# Peggy_Receiver.net
KiCad netlist of a schematic drawn in Altium Designer
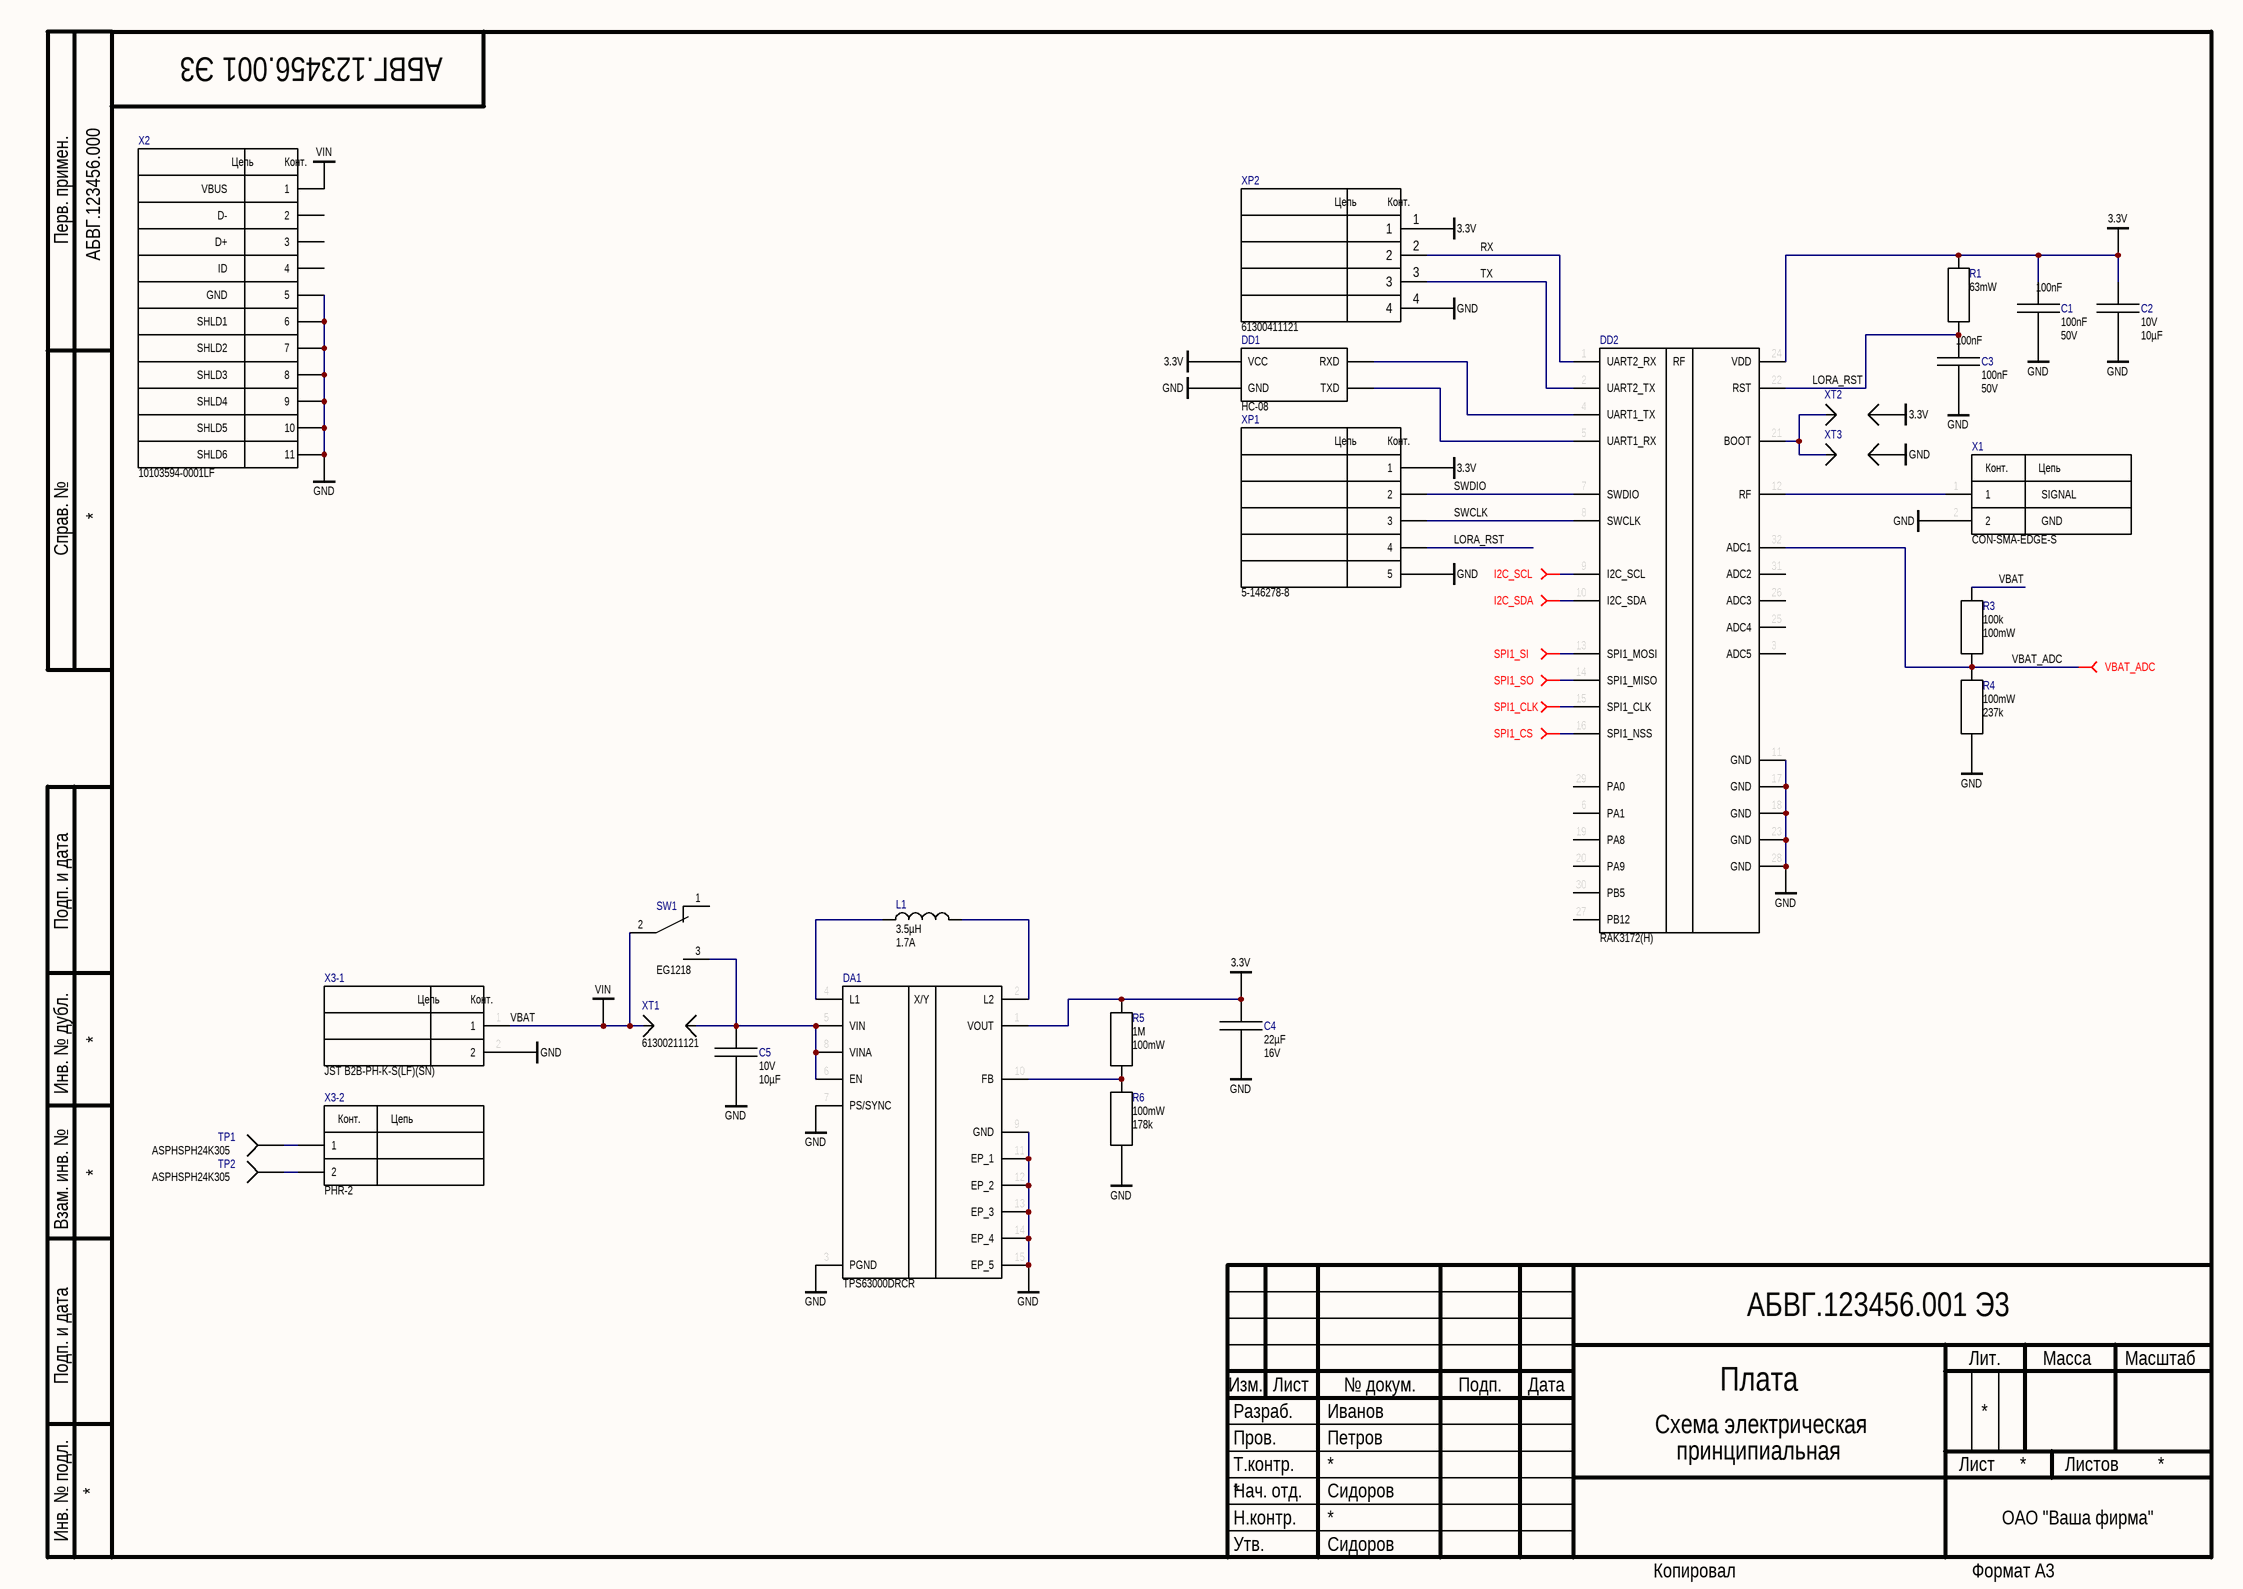
[diagram p0: Принципиальная схема Peggy Receiver.SchDoc]

(export (version "E")
  (design (tool "Eeschema 10.0.6"))
  (components
    (comp (ref "C1")
      (value "100nF")
      (footprint "CAPC1608X09M")
      (description "CAP CER 0.1UF 50V X7R 0603")
      (fields
        (field (name "VOLTAGE RATING") "50V")
        (field (name "TOLERANCE") "10%")
        (field (name "MANUFACTURER PART NUMBER") "GCM188R71H104KA57D")
        (field (name "CAPACITANCE") "100nF")
        (field (name "SOURCE") "Meteo_1.SCHLIB")
      )
      (libsource (lib "Sergek Concord Server") (part "CAP-NP-2"))
    )
    (comp (ref "C2")
      (value "10µF")
      (footprint "CAPC1608X87X35ML15T15")
      (description "Cap Ceramic 10uF 10V X5R 20% SMD 0603 85°C Paper T/R")
      (fields
        (field (name "VOLTAGE RATING") "10V")
        (field (name "TOLERANCE") "20%")
        (field (name "MANUFACTURER") "KEMET")
      )
      (libsource (lib "Sergek Concord Server") (part "CAP-NP-2"))
    )
    (comp (ref "C3")
      (value "100nF")
      (footprint "CAPC1608X09M")
      (description "CAP CER 0.1UF 50V X7R 0603")
      (fields
        (field (name "VOLTAGE RATING") "50V")
        (field (name "TOLERANCE") "10%")
        (field (name "MANUFACTURER PART NUMBER") "GCM188R71H104KA57D")
        (field (name "CAPACITANCE") "100nF")
        (field (name "SOURCE") "Meteo_1.SCHLIB")
      )
      (libsource (lib "Sergek Concord Server") (part "CAP-NP-2"))
    )
    (comp (ref "C4")
      (value "22µF")
      (footprint "CAPC2013X140X45ML15T25")
      (fields
        (field (name "VOLTAGE RATING") "16V")
        (field (name "TOLERANCE") "10%")
        (field (name "MANUFACTURER PART NUMBER") "C2012X5R1C226K125AC")
        (field (name "MANUFACTURER") "TDK")
      )
      (libsource (lib "Sergek Concord Server") (part "CAP-NP-2"))
    )
    (comp (ref "C5")
      (value "10µF")
      (footprint "CAPC1608X87X35ML15T15")
      (description "Cap Ceramic 10uF 10V X5R 20% SMD 0603 85°C Paper T/R")
      (fields
        (field (name "VOLTAGE RATING") "10V")
        (field (name "TOLERANCE") "20%")
        (field (name "MANUFACTURER") "KEMET")
      )
      (libsource (lib "Sergek Concord Server") (part "CAP-NP-2"))
    )
    (comp (ref "DA1")
      (value "TPS63000IDRCRQ1")
      (footprint "TPS63002DRCR")
      (description "IC REG BUCK BOOST ADJ 1.6A 10SON")
      (fields
        (field (name "MANUFACTURER PART NUMBER") "TPS63000DRCR")
        (field (name "MANUFACTURER") "Texas Instruments")
      )
      (libsource (lib "Sergek Concord Server") (part "TPS63000"))
    )
    (comp (ref "DD1")
      (value "HC-08")
      (footprint "HC-08")
      (description "Bluetooth 4.0 Module")
      (fields (field (name "MANUFACTURER PART NUMBER") "HC-08"))
      (libsource (lib "Sergek Concord Server") (part "HC-08"))
    )
    (comp (ref "DD2")
      (value "RAK3172(H)")
      (footprint "RAK3172(H)-Footprint-1")
      (description "RAK3172 WisDuo LPWAN Module")
      (fields
        (field (name "MANUFACTURER PART NUMBER") "RAK3172(H)")
        (field (name "MANUFACTURER") "RAK Wireless")
      )
      (libsource (lib "Sergek Concord Server") (part "RAK3172(H)"))
    )
    (comp (ref "I2C_SCL")
      (value "TP_1MM")
      (footprint "New footprint 1")
      (description "Test Point, 1mm diam")
      (fields (field (name "MANUFACTURER") "SRG_DEV"))
      (libsource (lib "Sergek Concord Server") (part "TP_1MM"))
    )
    (comp (ref "I2C_SDA")
      (value "TP_1MM")
      (footprint "New footprint 1")
      (description "Test Point, 1mm diam")
      (fields (field (name "MANUFACTURER") "SRG_DEV"))
      (libsource (lib "Sergek Concord Server") (part "TP_1MM"))
    )
    (comp (ref "L1")
      (value "3.5µH")
      (footprint "SRU5018680Y")
      (description "Ind Power Shielded Wirewound 3.5uH 30% 100KHz 9Q-Factor Ferrite 2.1A T/R")
      (fields
        (field (name "TOLERANCE") "30%")
        (field (name "SATURATION CURRENT") "1.7A")
        (field (name "MANUFACTURER") "Bourns")
      )
      (libsource (lib "Sergek Concord Server") (part "IND-2"))
    )
    (comp (ref "R1")
      (value "RNCF0603BTE10K0")
      (footprint "RESC1608X55X25ML10T15")
      (description "RES 10K OHM 0.1% 1/16W 0603")
      (fields (field (name "TOLERANCE") "0.1%") (field (name "POWER RATING") "63mW"))
      (libsource (lib "") (part "RES-2_1"))
    )
    (comp (ref "R3")
      (value "RMCF0603FT100K")
      (footprint "RESC1608X55X25ML10T15")
      (description "RES 100K OHM 1% 1/10W 0603")
      (fields
        (field (name "RESISTANCE") "100k")
        (field (name "MANUFACTURER") "Stackpole Electronics Inc")
        (field (name "TOLERANCE") "1%")
        (field (name "POWER RATING") "100mW")
      )
      (libsource (lib "Sergek Concord Server") (part "RES-2"))
    )
    (comp (ref "R4")
      (value "ERJ-3EKF2373V")
      (footprint "RESC1608X55X25ML10T15")
      (description "RES SMD 237K OHM 1% 1/10W 0603")
      (fields
        (field (name "POWER RATING") "100mW")
        (field (name "RESISTANCE") "237k")
        (field (name "TOLERANCE") "1%")
        (field (name "MANUFACTURER") "Panasonic")
      )
      (libsource (lib "Sergek Concord Server") (part "RES-2"))
    )
    (comp (ref "R5")
      (value "1M")
      (footprint "RESC1608X95X40ML15T20")
      (description "RES 1M OHM 5% 1/10W 0603")
      (fields
        (field (name "POWER RATING") "100mW")
        (field (name "TOLERANCE") "5%")
        (field (name "MANUFACTURER PART NUMBER") "RMCF0603JT1M00")
      )
      (libsource (lib "Sergek Concord Server") (part "RES-2"))
    )
    (comp (ref "R6")
      (value "178k")
      (footprint "RESC1608X95X40ML15T20")
      (fields
        (field (name "TOLERANCE") "1%")
        (field (name "POWER RATING") "100mW")
        (field (name "MANUFACTURER PART NUMBER") "ERJ-3EKF1783V")
        (field (name "MANUFACTURER") "Panasonic")
      )
      (libsource (lib "Sergek Concord Server") (part "RES-2"))
    )
    (comp (ref "SPI1_CLK")
      (value "TP_1MM")
      (footprint "New footprint 1")
      (description "Test Point, 1mm diam")
      (fields (field (name "MANUFACTURER") "SRG_DEV"))
      (libsource (lib "Sergek Concord Server") (part "TP_1MM"))
    )
    (comp (ref "SPI1_CS")
      (value "TP_1MM")
      (footprint "New footprint 1")
      (description "Test Point, 1mm diam")
      (fields (field (name "MANUFACTURER") "SRG_DEV"))
      (libsource (lib "Sergek Concord Server") (part "TP_1MM"))
    )
    (comp (ref "SPI1_SI")
      (value "TP_1MM")
      (footprint "New footprint 1")
      (description "Test Point, 1mm diam")
      (fields (field (name "MANUFACTURER") "SRG_DEV"))
      (libsource (lib "Sergek Concord Server") (part "TP_1MM"))
    )
    (comp (ref "SPI1_SO")
      (value "TP_1MM")
      (footprint "New footprint 1")
      (description "Test Point, 1mm diam")
      (fields (field (name "MANUFACTURER") "SRG_DEV"))
      (libsource (lib "Sergek Concord Server") (part "TP_1MM"))
    )
    (comp (ref "SW1")
      (value "EG1218")
      (footprint "ESWI-EG1218_V")
      (description "Slide Switch, SPDT, 500 V, -20 to 70 degC, 3-Pin THD, RoHS, Bulk")
      (fields (field (name "MANUFACTURER") "E-Switch") (field (name "MANUFACTURER PART NUMBER") "EG1218"))
      (libsource (lib "Sergek Concord Server") (part "SW-SPDT-3_B"))
    )
    (comp (ref "TP1")
      (value "ASPHSPH24K305")
      (description "Black 24 AWG Jumper Lead Socket to Socket Tin 12.0")
      (fields
        (field (name "MANUFACTURER") "JST Sales America Inc.")
        (field (name "MANUFACTURER PART NUMBER") "ASPHSPH24K305")
      )
      (libsource (lib "Sergek Concord Server") (part "JST_Metal_Contact"))
    )
    (comp (ref "TP2")
      (value "ASPHSPH24K305")
      (description "Black 24 AWG Jumper Lead Socket to Socket Tin 12.0")
      (fields
        (field (name "MANUFACTURER") "JST Sales America Inc.")
        (field (name "MANUFACTURER PART NUMBER") "ASPHSPH24K305")
      )
      (libsource (lib "Sergek Concord Server") (part "JST_Metal_Contact"))
    )
    (comp (ref "VBAT_ADC")
      (value "TP_1MM")
      (footprint "New footprint 1")
      (description "Test Point, 1mm diam")
      (fields (field (name "MANUFACTURER") "SRG_DEV"))
      (libsource (lib "Sergek Concord Server") (part "TP_1MM"))
    )
    (comp (ref "X1")
      (value "CON-SMA-EDGE-S")
      (footprint "RFSOLUTIONS_CON-SMA-EDGE-S")
      (description "CONN SMA JACK STR EDGE MNT")
      (fields
        (field (name "MANUFACTURER PART NUMBER") "CON-SMA-EDGE-S")
        (field (name "MANUFACTURER") "RF Solutions")
      )
      (libsource (lib "Sergek Concord Server") (part "CON-SMA-EDGE-S"))
    )
    (comp (ref "X2")
      (value "10103594-0001LF")
      (footprint "FCI-10103594-0001LF_V")
      (description "Micro USB 2.0 B Receptacle, 5 Position, Height 3.24 mm, -55 to 85 degC, RoHS, Tape and Reel")
      (fields
        (field (name "MANUFACTURER PART NUMBER") "10103594-0001LF")
        (field (name "MANUFACTURER") "Amphenol ICC (FCI)")
      )
      (libsource (lib "Sergek Concord Server") (part "USB-5-6SHLD"))
    )
    (comp (ref "X3-1")
      (value "B2B-PH-K-S")
      (footprint "JST-S2B-PH-K-S_V")
      (description "CONN HEADER VERT 2POS 2MM")
      (fields
        (field (name "MANUFACTURER PART NUMBER") "JST B2B-PH-K-S(LF)(SN)")
        (field (name "MANUFACTURER") "Japan Solderless Terminals")
      )
      (libsource (lib "Sergek Concord Server") (part "CN-1P-M-R2"))
    )
    (comp (ref "X3-2")
      (value "PHR-2")
      (description "CONN HOUSING PH 2POS 2MM WHITE")
      (fields (field (name "MANUFACTURER") "JST") (field (name "MANUFACTURER PART NUMBER") "PHR-2"))
      (libsource (lib "Sergek Concord Server") (part "X-2"))
    )
    (comp (ref "XP1")
      (value "5-146278-5")
      (footprint "5-146278-8-Footprint-1")
      (description "Conn Unshrouded Header HDR 5 POS 2.54mm Solder ST Thru-Hole Carton")
      (fields
        (field (name "MANUFACTURER PART NUMBER") "5-146278-8")
        (field (name "MANUFACTURER") "TE Connectivity")
      )
      (libsource (lib "Sergek Concord Server") (part "XP-5"))
    )
    (comp (ref "XP2")
      (value "61300411121")
      (footprint "20021311-00010T4LF-Footprint-1")
      (description "Conn Unshrouded Header HDR 4 POS 2.54mm Solder ST Thru-Hole Bag")
      (fields
        (field (name "MANUFACTURER") "Würth Elektronik")
        (field (name "MANUFACTURER PART NUMBER") "61300411121")
      )
      (libsource (lib "Sergek Concord Server") (part "XP-4"))
    )
    (comp (ref "XT1")
      (value "Jumper_1x2")
      (footprint "CON%3A PLS-2")
      (fields
        (field (name "MANUFACTURER") "Wurth Electronics")
        (field (name "MANUFACTURER PART NUMBER") "61300211121")
      )
      (libsource (lib "Sergek Concord Server") (part "Jumper 1x2"))
    )
    (comp (ref "XT2")
      (value "Jumper_solderable")
      (footprint "JUMPER-Footprint-2")
      (description "Solderable Jumper")
      (fields (field (name "MANUFACTURER PART NUMBER") "Home made"))
      (libsource (lib "Sergek Concord Server") (part "Jumper 1x2"))
    )
    (comp (ref "XT3")
      (value "Jumper_solderable")
      (footprint "JUMPER-Footprint-2")
      (description "Solderable Jumper")
      (fields (field (name "MANUFACTURER PART NUMBER") "Home made"))
      (libsource (lib "Sergek Concord Server") (part "Jumper 1x2"))
    )
  )
  (nets
    (net (code "1") (name "/LORA_RST") (class "Default")
      (node (ref "C3") (pin "2") (pinfunction "2_2") (pintype "passive"))
      (node (ref "DD2") (pin "22") (pinfunction "RST_22") (pintype "passive"))
      (node (ref "R1") (pin "2") (pinfunction "2_2") (pintype "passive"))
      (node (ref "XP1") (pin "4") (pinfunction "4_4") (pintype "passive"))
    )
    (net (code "2") (name "/RX") (class "Default")
      (node (ref "DD2") (pin "1") (pinfunction "UART2_RX_1") (pintype "passive"))
      (node (ref "XP2") (pin "2") (pinfunction "2_2") (pintype "passive"))
    )
    (net (code "3") (name "/SWCLK") (class "Default")
      (node (ref "DD2") (pin "8") (pinfunction "SWCLK_8") (pintype "passive"))
      (node (ref "XP1") (pin "3") (pinfunction "3_3") (pintype "passive"))
    )
    (net (code "4") (name "/SWDIO") (class "Default")
      (node (ref "DD2") (pin "7") (pinfunction "SWDIO_7") (pintype "passive"))
      (node (ref "XP1") (pin "2") (pinfunction "2_2") (pintype "passive"))
    )
    (net (code "5") (name "/TX") (class "Default")
      (node (ref "DD2") (pin "2") (pinfunction "UART2_TX_2") (pintype "passive"))
      (node (ref "XP2") (pin "3") (pinfunction "3_3") (pintype "passive"))
    )
    (net (code "6") (name "/VBAT_ADC") (class "Default")
      (node (ref "DD2") (pin "32") (pinfunction "ADC1_32") (pintype "passive"))
      (node (ref "R3") (pin "1") (pinfunction "1_1") (pintype "passive"))
      (node (ref "R4") (pin "2") (pinfunction "2_2") (pintype "passive"))
      (node (ref "VBAT_ADC") (pin "1") (pinfunction "1_1") (pintype "passive"))
    )
    (net (code "7") (name "3.3V") (class "Default")
      (node (ref "C1") (pin "2") (pinfunction "2_2") (pintype "passive"))
      (node (ref "C2") (pin "2") (pinfunction "2_2") (pintype "passive"))
      (node (ref "C4") (pin "2") (pinfunction "2_2") (pintype "passive"))
      (node (ref "DA1") (pin "1") (pinfunction "VOUT_1") (pintype "passive"))
      (node (ref "DD1") (pin "1") (pinfunction "VCC_1") (pintype "passive"))
      (node (ref "DD2") (pin "24") (pinfunction "VDD_24") (pintype "passive"))
      (node (ref "R1") (pin "1") (pinfunction "1_1") (pintype "passive"))
      (node (ref "R5") (pin "2") (pinfunction "2_2") (pintype "passive"))
      (node (ref "XP1") (pin "1") (pinfunction "1_1") (pintype "passive"))
      (node (ref "XP2") (pin "1") (pinfunction "1_1") (pintype "passive"))
      (node (ref "XT2") (pin "2") (pinfunction "2_2") (pintype "passive"))
    )
    (net (code "8") (name "GND") (class "Default")
      (node (ref "C1") (pin "1") (pinfunction "1_1") (pintype "passive"))
      (node (ref "C2") (pin "1") (pinfunction "1_1") (pintype "passive"))
      (node (ref "C3") (pin "1") (pinfunction "1_1") (pintype "passive"))
      (node (ref "C4") (pin "1") (pinfunction "1_1") (pintype "passive"))
      (node (ref "C5") (pin "1") (pinfunction "1_1") (pintype "passive"))
      (node (ref "DA1") (pin "11") (pinfunction "EP_1_11") (pintype "passive"))
      (node (ref "DA1") (pin "12") (pinfunction "EP_2_12") (pintype "passive"))
      (node (ref "DA1") (pin "13") (pinfunction "EP_3_13") (pintype "passive"))
      (node (ref "DA1") (pin "14") (pinfunction "EP_4_14") (pintype "passive"))
      (node (ref "DA1") (pin "15") (pinfunction "EP_5_15") (pintype "passive"))
      (node (ref "DA1") (pin "3") (pinfunction "PGND_3") (pintype "passive"))
      (node (ref "DA1") (pin "7") (pinfunction "PS/SYNC_7") (pintype "passive"))
      (node (ref "DA1") (pin "9") (pinfunction "GND_9") (pintype "passive"))
      (node (ref "DD1") (pin "2") (pinfunction "GND_2") (pintype "passive"))
      (node (ref "DD2") (pin "11") (pinfunction "GND_11") (pintype "passive"))
      (node (ref "DD2") (pin "17") (pinfunction "GND_17") (pintype "passive"))
      (node (ref "DD2") (pin "18") (pinfunction "GND_18") (pintype "passive"))
      (node (ref "DD2") (pin "23") (pinfunction "GND_23") (pintype "passive"))
      (node (ref "DD2") (pin "28") (pinfunction "GND_28") (pintype "passive"))
      (node (ref "R4") (pin "1") (pinfunction "1_1") (pintype "passive"))
      (node (ref "R6") (pin "1") (pinfunction "1_1") (pintype "passive"))
      (node (ref "X1") (pin "2") (pinfunction "GND_2") (pintype "passive"))
      (node (ref "X2") (pin "10") (pinfunction "SHLD5_10") (pintype "passive"))
      (node (ref "X2") (pin "11") (pinfunction "SHLD6_11") (pintype "passive"))
      (node (ref "X2") (pin "5") (pinfunction "GND_5") (pintype "passive"))
      (node (ref "X2") (pin "6") (pinfunction "SHLD1_6") (pintype "passive"))
      (node (ref "X2") (pin "7") (pinfunction "SHLD2_7") (pintype "passive"))
      (node (ref "X2") (pin "8") (pinfunction "SHLD3_8") (pintype "passive"))
      (node (ref "X2") (pin "9") (pinfunction "SHLD4_9") (pintype "passive"))
      (node (ref "X3-1") (pin "2") (pinfunction "2_2") (pintype "passive"))
      (node (ref "XP1") (pin "5") (pinfunction "5_5") (pintype "passive"))
      (node (ref "XP2") (pin "4") (pinfunction "4_4") (pintype "passive"))
      (node (ref "XT3") (pin "2") (pinfunction "2_2") (pintype "passive"))
    )
    (net (code "9") (name "Net-(DA1-EN)") (class "Default")
      (node (ref "C5") (pin "2") (pinfunction "2_2") (pintype "passive"))
      (node (ref "DA1") (pin "5") (pinfunction "VIN_5") (pintype "passive"))
      (node (ref "DA1") (pin "6") (pinfunction "EN_6") (pintype "passive"))
      (node (ref "DA1") (pin "8") (pinfunction "VINA_8") (pintype "passive"))
      (node (ref "SW1") (pin "3") (pinfunction "3_3") (pintype "passive"))
      (node (ref "XT1") (pin "2") (pinfunction "2_2") (pintype "passive"))
    )
    (net (code "10") (name "Net-(DA1-FB)") (class "Default")
      (node (ref "DA1") (pin "10") (pinfunction "FB_10") (pintype "passive"))
      (node (ref "R5") (pin "1") (pinfunction "1_1") (pintype "passive"))
      (node (ref "R6") (pin "2") (pinfunction "2_2") (pintype "passive"))
    )
    (net (code "11") (name "Net-(DA1-L1)") (class "Default")
      (node (ref "DA1") (pin "4") (pinfunction "L1_4") (pintype "passive"))
      (node (ref "L1") (pin "1") (pinfunction "1_1") (pintype "passive"))
    )
    (net (code "12") (name "Net-(DA1-L2)") (class "Default")
      (node (ref "DA1") (pin "2") (pinfunction "L2_2") (pintype "passive"))
      (node (ref "L1") (pin "2") (pinfunction "2_2") (pintype "passive"))
    )
    (net (code "13") (name "Net-(DD1-RXD)") (class "Default")
      (node (ref "DD1") (pin "4") (pinfunction "RXD_4") (pintype "passive"))
      (node (ref "DD2") (pin "4") (pinfunction "UART1_TX_4") (pintype "passive"))
    )
    (net (code "14") (name "Net-(DD1-TXD)") (class "Default")
      (node (ref "DD1") (pin "3") (pinfunction "TXD_3") (pintype "passive"))
      (node (ref "DD2") (pin "5") (pinfunction "UART1_RX_5") (pintype "passive"))
    )
    (net (code "15") (name "Net-(DD2-BOOT)") (class "Default")
      (node (ref "DD2") (pin "21") (pinfunction "BOOT_21") (pintype "passive"))
      (node (ref "XT2") (pin "1") (pinfunction "1_1") (pintype "passive"))
      (node (ref "XT3") (pin "1") (pinfunction "1_1") (pintype "passive"))
    )
    (net (code "16") (name "Net-(DD2-I2C_SCL)") (class "Default")
      (node (ref "DD2") (pin "9") (pinfunction "I2C_SCL_9") (pintype "passive"))
      (node (ref "I2C_SCL") (pin "1") (pinfunction "1_1") (pintype "passive"))
    )
    (net (code "17") (name "Net-(DD2-I2C_SDA)") (class "Default")
      (node (ref "DD2") (pin "10") (pinfunction "I2C_SDA_10") (pintype "passive"))
      (node (ref "I2C_SDA") (pin "1") (pinfunction "1_1") (pintype "passive"))
    )
    (net (code "18") (name "Net-(DD2-RF)") (class "Default")
      (node (ref "DD2") (pin "12") (pinfunction "RF_12") (pintype "passive"))
      (node (ref "X1") (pin "1") (pinfunction "SIGNAL_1") (pintype "passive"))
    )
    (net (code "19") (name "Net-(DD2-SPI1_CLK)") (class "Default")
      (node (ref "DD2") (pin "15") (pinfunction "SPI1_CLK_15") (pintype "passive"))
      (node (ref "SPI1_CLK") (pin "1") (pinfunction "1_1") (pintype "passive"))
    )
    (net (code "20") (name "Net-(DD2-SPI1_MISO)") (class "Default")
      (node (ref "DD2") (pin "14") (pinfunction "SPI1_MISO_14") (pintype "passive"))
      (node (ref "SPI1_SO") (pin "1") (pinfunction "1_1") (pintype "passive"))
    )
    (net (code "21") (name "Net-(DD2-SPI1_MOSI)") (class "Default")
      (node (ref "DD2") (pin "13") (pinfunction "SPI1_MOSI_13") (pintype "passive"))
      (node (ref "SPI1_SI") (pin "1") (pinfunction "1_1") (pintype "passive"))
    )
    (net (code "22") (name "Net-(DD2-SPI1_NSS)") (class "Default")
      (node (ref "DD2") (pin "16") (pinfunction "SPI1_NSS_16") (pintype "passive"))
      (node (ref "SPI1_CS") (pin "1") (pinfunction "1_1") (pintype "passive"))
    )
    (net (code "23") (name "Net-(TP1-Pad1)") (class "Default")
      (node (ref "TP1") (pin "1") (pinfunction "1_1") (pintype "passive"))
      (node (ref "X3-2") (pin "1") (pinfunction "1_1") (pintype "passive"))
    )
    (net (code "24") (name "Net-(TP2-Pad1)") (class "Default")
      (node (ref "TP2") (pin "1") (pinfunction "1_1") (pintype "passive"))
      (node (ref "X3-2") (pin "2") (pinfunction "2_2") (pintype "passive"))
    )
    (net (code "25") (name "VIN") (class "Default")
      (node (ref "R3") (pin "2") (pinfunction "2_2") (pintype "passive"))
      (node (ref "SW1") (pin "2") (pinfunction "COM_2") (pintype "passive"))
      (node (ref "X2") (pin "1") (pinfunction "VBUS_1") (pintype "passive"))
      (node (ref "X3-1") (pin "1") (pinfunction "1_1") (pintype "passive"))
      (node (ref "XT1") (pin "1") (pinfunction "1_1") (pintype "passive"))
    )
    (net (code "26") (name "unconnected-(DD2-ADC2-Pad31)") (class "Default")
      (node (ref "DD2") (pin "31") (pinfunction "ADC2_31") (pintype "passive"))
    )
    (net (code "27") (name "unconnected-(DD2-ADC3-Pad26)") (class "Default")
      (node (ref "DD2") (pin "26") (pinfunction "ADC3_26") (pintype "passive"))
    )
    (net (code "28") (name "unconnected-(DD2-ADC4-Pad25)") (class "Default")
      (node (ref "DD2") (pin "25") (pinfunction "ADC4_25") (pintype "passive"))
    )
    (net (code "29") (name "unconnected-(DD2-ADC5-Pad3)") (class "Default")
      (node (ref "DD2") (pin "3") (pinfunction "ADC5_3") (pintype "passive"))
    )
    (net (code "30") (name "unconnected-(DD2-PA0-Pad29)") (class "Default")
      (node (ref "DD2") (pin "29") (pinfunction "PA0_29") (pintype "passive"))
    )
    (net (code "31") (name "unconnected-(DD2-PA1-Pad6)") (class "Default")
      (node (ref "DD2") (pin "6") (pinfunction "PA1_6") (pintype "passive"))
    )
    (net (code "32") (name "unconnected-(DD2-PA8-Pad19)") (class "Default")
      (node (ref "DD2") (pin "19") (pinfunction "PA8_19") (pintype "passive"))
    )
    (net (code "33") (name "unconnected-(DD2-PA9-Pad20)") (class "Default")
      (node (ref "DD2") (pin "20") (pinfunction "PA9_20") (pintype "passive"))
    )
    (net (code "34") (name "unconnected-(DD2-PB5-Pad30)") (class "Default")
      (node (ref "DD2") (pin "30") (pinfunction "PB5_30") (pintype "passive"))
    )
    (net (code "35") (name "unconnected-(DD2-PB12-Pad27)") (class "Default")
      (node (ref "DD2") (pin "27") (pinfunction "PB12_27") (pintype "passive"))
    )
    (net (code "36") (name "unconnected-(SW1-Pad1)") (class "Default")
      (node (ref "SW1") (pin "1") (pinfunction "1_1") (pintype "passive"))
    )
    (net (code "37") (name "unconnected-(X2-D+-Pad3)") (class "Default")
      (node (ref "X2") (pin "3") (pinfunction "D+_3") (pintype "passive"))
    )
    (net (code "38") (name "unconnected-(X2-D--Pad2)") (class "Default")
      (node (ref "X2") (pin "2") (pinfunction "D-_2") (pintype "passive"))
    )
    (net (code "39") (name "unconnected-(X2-ID-Pad4)") (class "Default")
      (node (ref "X2") (pin "4") (pinfunction "ID_4") (pintype "passive"))
    )
  )
)
